# LoRa-Bee_v12.net
KiCad netlist of a schematic drawn in EAGLE
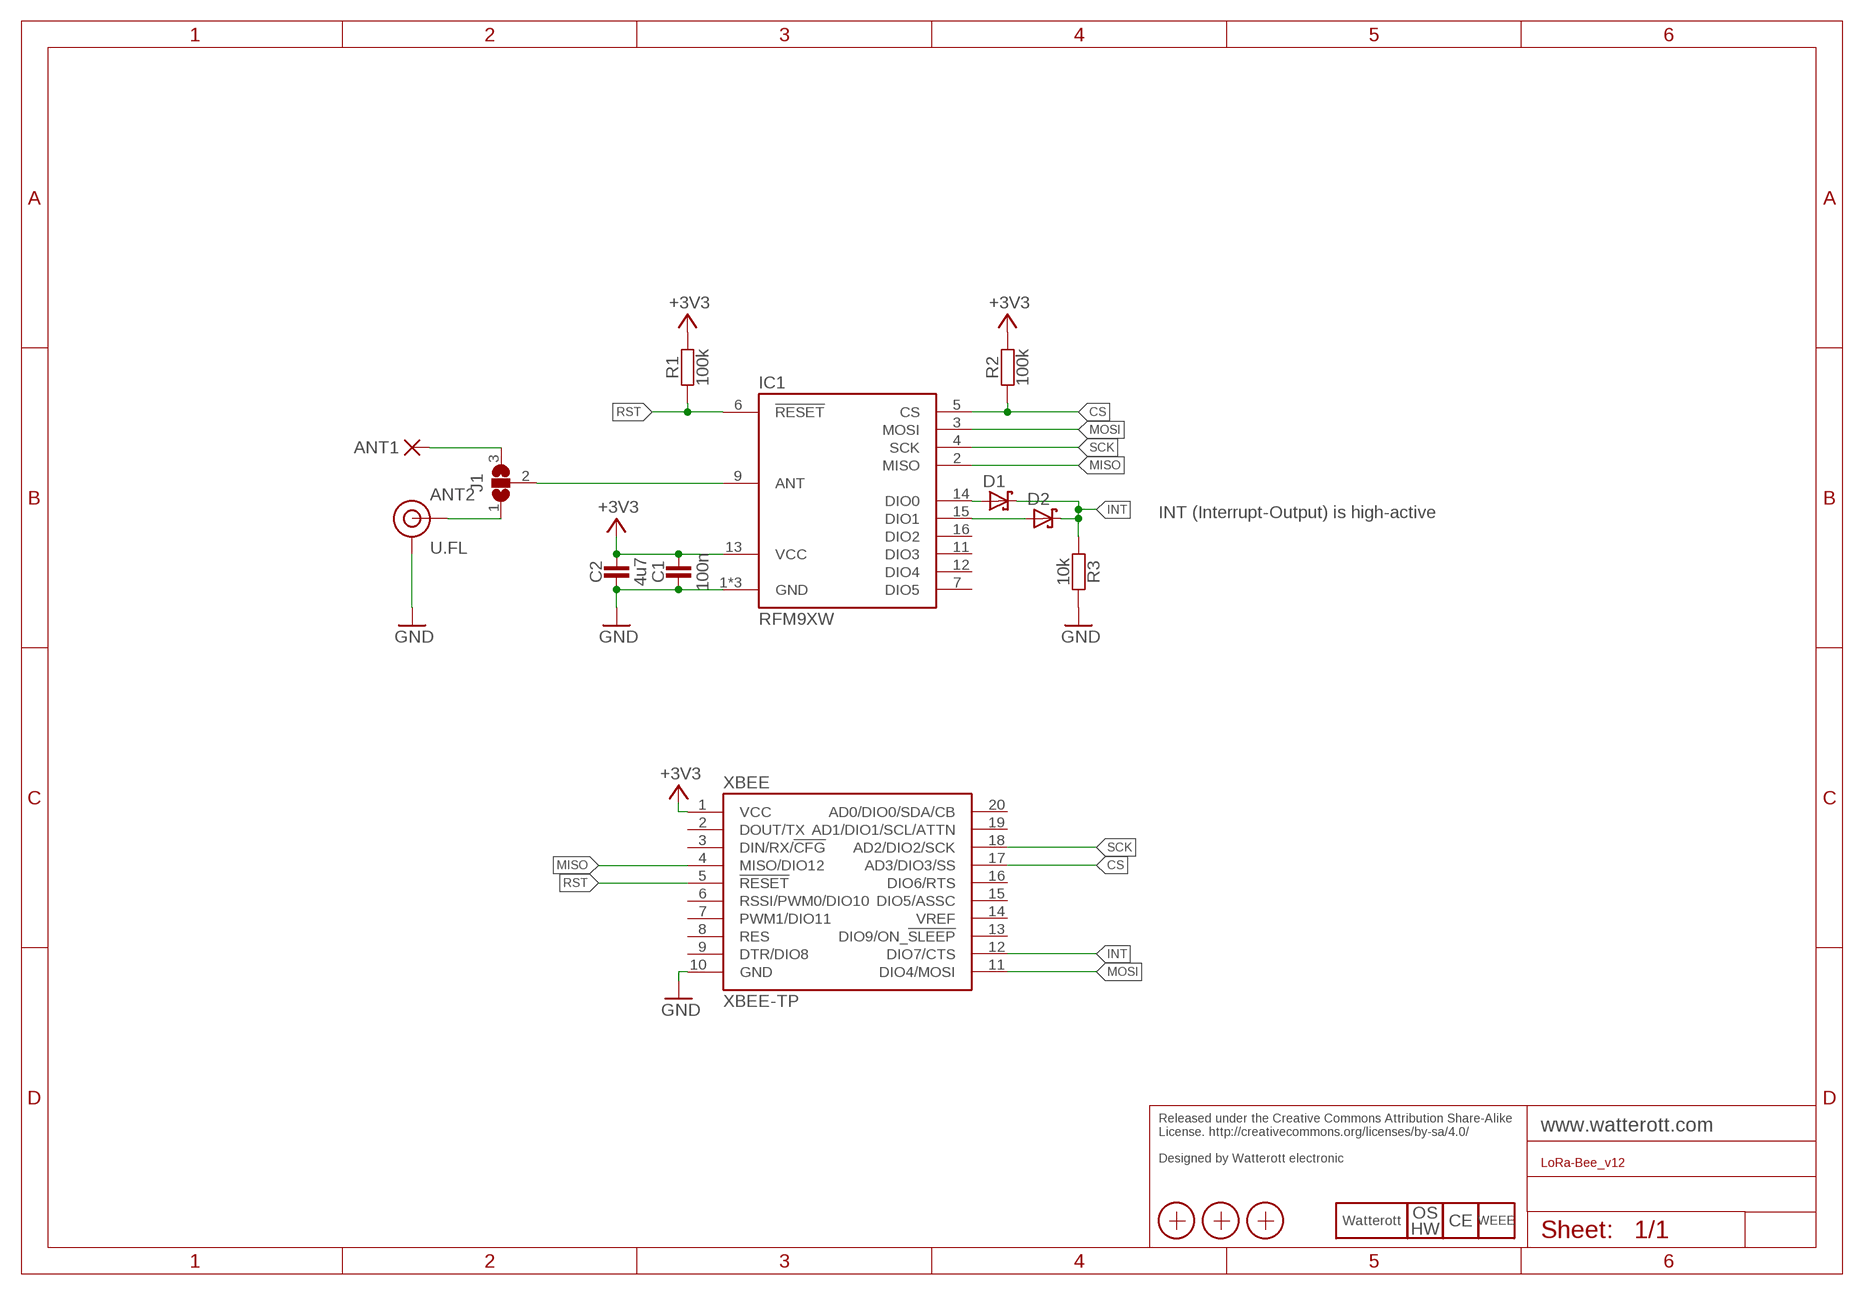
[diagram p0: schematic, sheet 1]

(export (version "E")
  (design (tool "Eeschema 10.0.6"))
  (components
    (comp (ref "ANT1")
      (value "PAD-1.00-1.60")
      (footprint "eagle-import:PAD-1.00-1.60")
      (libsource (lib "eagle-import") (part "PAD-1.00-1.60"))
    )
    (comp (ref "ANT2")
      (value "U.FL")
      (footprint "eagle-import:U.FL")
      (libsource (lib "eagle-import") (part "U.FL"))
    )
    (comp (ref "C1")
      (value "100n")
      (footprint "eagle-import:C0402")
      (libsource (lib "eagle-import") (part "CAPACITOR-0402"))
    )
    (comp (ref "C2")
      (value "4u7")
      (footprint "eagle-import:C0402")
      (libsource (lib "eagle-import") (part "CAPACITOR-0402"))
    )
    (comp (ref "D1")
      (value "D_SCHOTTKY-SOD532")
      (footprint "eagle-import:SOD523")
      (libsource (lib "eagle-import") (part "D_SCHOTTKY-SOD532"))
    )
    (comp (ref "D2")
      (value "D_SCHOTTKY-SOD532")
      (footprint "eagle-import:SOD523")
      (libsource (lib "eagle-import") (part "D_SCHOTTKY-SOD532"))
    )
    (comp (ref "IC1")
      (value "RFM9XW")
      (footprint "eagle-import:RFM9X")
      (libsource (lib "eagle-import") (part "RFM9XW"))
    )
    (comp (ref "J1")
      (value "JUMPER3-0603")
      (footprint "eagle-import:JUMPER3-0603")
      (libsource (lib "eagle-import") (part "JUMPER3-0603"))
    )
    (comp (ref "LOGO3")
      (value "LOGO_SPARK-2")
      (footprint "eagle-import:SPARK_2MM")
      (libsource (lib "eagle-import") (part "LOGO_SPARK-2"))
    )
    (comp (ref "LOGO4")
      (value "LOGO_OSHW-2")
      (footprint "eagle-import:OSHW_2MM")
      (libsource (lib "eagle-import") (part "LOGO_OSHW-2"))
    )
    (comp (ref "LOGO5")
      (value "LOGO_CE-2")
      (footprint "eagle-import:CE_2MM")
      (libsource (lib "eagle-import") (part "LOGO_CE-2"))
    )
    (comp (ref "LOGO6")
      (value "LOGO_WEEE-4")
      (footprint "eagle-import:WEEE_4MM")
      (libsource (lib "eagle-import") (part "LOGO_WEEE-4"))
    )
    (comp (ref "R1")
      (value "100k")
      (footprint "eagle-import:C0402")
      (libsource (lib "eagle-import") (part "RESISTOR-0402"))
    )
    (comp (ref "R2")
      (value "100k")
      (footprint "eagle-import:C0402")
      (libsource (lib "eagle-import") (part "RESISTOR-0402"))
    )
    (comp (ref "R3")
      (value "10k")
      (footprint "eagle-import:C0402")
      (libsource (lib "eagle-import") (part "RESISTOR-0402"))
    )
    (comp (ref "X1")
      (value "PASSER-07")
      (footprint "eagle-import:PASSER_07MM")
      (libsource (lib "eagle-import") (part "PASSER-07"))
    )
    (comp (ref "X2")
      (value "PASSER-07")
      (footprint "eagle-import:PASSER_07MM")
      (libsource (lib "eagle-import") (part "PASSER-07"))
    )
    (comp (ref "X3")
      (value "PASSER-07")
      (footprint "eagle-import:PASSER_07MM")
      (libsource (lib "eagle-import") (part "PASSER-07"))
    )
    (comp (ref "XBEE")
      (value "XBEE-TP")
      (footprint "eagle-import:XBEE_TP")
      (libsource (lib "eagle-import") (part "XBEE-TP"))
    )
  )
  (nets
    (net (code "1") (name "+3V3") (class "Default")
      (node (ref "C1") (pin "2") (pinfunction "2_2") (pintype "passive"))
      (node (ref "C2") (pin "2") (pinfunction "2_2") (pintype "passive"))
      (node (ref "IC1") (pin "13") (pinfunction "VCC_13") (pintype "power_in"))
      (node (ref "R1") (pin "2") (pinfunction "2_2") (pintype "passive"))
      (node (ref "R2") (pin "2") (pinfunction "2_2") (pintype "passive"))
      (node (ref "XBEE") (pin "1") (pinfunction "VCC_1") (pintype "power_in"))
    )
    (net (code "2") (name "CS") (class "Default")
      (node (ref "IC1") (pin "5") (pinfunction "CS_5") (pintype "input"))
      (node (ref "R2") (pin "1") (pinfunction "1_1") (pintype "passive"))
      (node (ref "XBEE") (pin "17") (pinfunction "AD3/DIO3/SS_17") (pintype "bidirectional"))
    )
    (net (code "3") (name "GND") (class "Default")
      (node (ref "ANT2") (pin "1") (pinfunction "GND_1") (pintype "bidirectional"))
      (node (ref "ANT2") (pin "2") (pinfunction "GND_2") (pintype "bidirectional"))
      (node (ref "C1") (pin "1") (pinfunction "1_1") (pintype "passive"))
      (node (ref "C2") (pin "1") (pinfunction "1_1") (pintype "passive"))
      (node (ref "IC1") (pin "1") (pinfunction "GND_1") (pintype "power_in"))
      (node (ref "IC1") (pin "10") (pinfunction "GND_10") (pintype "power_in"))
      (node (ref "IC1") (pin "8") (pinfunction "GND_8") (pintype "power_in"))
      (node (ref "R3") (pin "2") (pinfunction "2_2") (pintype "passive"))
      (node (ref "XBEE") (pin "10") (pinfunction "GND_10") (pintype "power_in"))
    )
    (net (code "4") (name "INT") (class "Default")
      (node (ref "D1") (pin "C") (pinfunction "C_C") (pintype "passive"))
      (node (ref "D2") (pin "C") (pinfunction "C_C") (pintype "passive"))
      (node (ref "R3") (pin "1") (pinfunction "1_1") (pintype "passive"))
      (node (ref "XBEE") (pin "12") (pinfunction "DIO7/CTS_12") (pintype "bidirectional"))
    )
    (net (code "5") (name "MISO") (class "Default")
      (node (ref "IC1") (pin "2") (pinfunction "MISO_2") (pintype "output"))
      (node (ref "XBEE") (pin "4") (pinfunction "MISO/DIO12_4") (pintype "bidirectional"))
    )
    (net (code "6") (name "MOSI") (class "Default")
      (node (ref "IC1") (pin "3") (pinfunction "MOSI_3") (pintype "input"))
      (node (ref "XBEE") (pin "11") (pinfunction "DIO4/MOSI_11") (pintype "bidirectional"))
    )
    (net (code "7") (name "Net-(ANT1-P)") (class "Default")
      (node (ref "ANT1") (pin "1") (pinfunction "P_1") (pintype "passive"))
      (node (ref "J1") (pin "3") (pinfunction "3_3") (pintype "passive"))
    )
    (net (code "8") (name "Net-(ANT2-SIGNAL)") (class "Default")
      (node (ref "ANT2") (pin "FEED") (pinfunction "SIGNAL_FEED") (pintype "bidirectional"))
      (node (ref "J1") (pin "1") (pinfunction "1_1") (pintype "passive"))
    )
    (net (code "9") (name "Net-(IC1-ANT)") (class "Default")
      (node (ref "IC1") (pin "9") (pinfunction "ANT_9") (pintype "bidirectional"))
      (node (ref "J1") (pin "2") (pinfunction "2_2") (pintype "passive"))
    )
    (net (code "10") (name "Net-(IC1-DIO0)") (class "Default")
      (node (ref "D1") (pin "A") (pinfunction "A_A") (pintype "passive"))
      (node (ref "IC1") (pin "14") (pinfunction "DIO0_14") (pintype "bidirectional"))
    )
    (net (code "11") (name "Net-(IC1-DIO1)") (class "Default")
      (node (ref "D2") (pin "A") (pinfunction "A_A") (pintype "passive"))
      (node (ref "IC1") (pin "15") (pinfunction "DIO1_15") (pintype "bidirectional"))
    )
    (net (code "12") (name "RST") (class "Default")
      (node (ref "IC1") (pin "6") (pinfunction "~{RESET}_6") (pintype "input"))
      (node (ref "R1") (pin "1") (pinfunction "1_1") (pintype "passive"))
      (node (ref "XBEE") (pin "5") (pinfunction "~{RESET}_5") (pintype "bidirectional"))
    )
    (net (code "13") (name "SCK") (class "Default")
      (node (ref "IC1") (pin "4") (pinfunction "SCK_4") (pintype "input"))
      (node (ref "XBEE") (pin "18") (pinfunction "AD2/DIO2/SCK_18") (pintype "bidirectional"))
    )
    (net (code "14") (name "unconnected-(IC1-DIO2-Pad16)") (class "Default")
      (node (ref "IC1") (pin "16") (pinfunction "DIO2_16") (pintype "bidirectional"))
    )
    (net (code "15") (name "unconnected-(IC1-DIO3-Pad11)") (class "Default")
      (node (ref "IC1") (pin "11") (pinfunction "DIO3_11") (pintype "bidirectional"))
    )
    (net (code "16") (name "unconnected-(IC1-DIO4-Pad12)") (class "Default")
      (node (ref "IC1") (pin "12") (pinfunction "DIO4_12") (pintype "bidirectional"))
    )
    (net (code "17") (name "unconnected-(IC1-DIO5-Pad7)") (class "Default")
      (node (ref "IC1") (pin "7") (pinfunction "DIO5_7") (pintype "bidirectional"))
    )
    (net (code "18") (name "unconnected-(XBEE-AD0{slash}DIO0{slash}SDA{slash}CB-Pad20)") (class "Default")
      (node (ref "XBEE") (pin "20") (pinfunction "AD0/DIO0/SDA/CB_20") (pintype "bidirectional"))
    )
    (net (code "19") (name "unconnected-(XBEE-AD1{slash}DIO1{slash}SCL{slash}ATTN-Pad19)") (class "Default")
      (node (ref "XBEE") (pin "19") (pinfunction "AD1/DIO1/SCL/ATTN_19") (pintype "bidirectional"))
    )
    (net (code "20") (name "unconnected-(XBEE-DIN{slash}RX{slash}~{CFG}-Pad3)") (class "Default")
      (node (ref "XBEE") (pin "3") (pinfunction "DIN/RX/~{CFG}_3") (pintype "bidirectional"))
    )
    (net (code "21") (name "unconnected-(XBEE-DIO5{slash}ASSC-Pad15)") (class "Default")
      (node (ref "XBEE") (pin "15") (pinfunction "DIO5/ASSC_15") (pintype "bidirectional"))
    )
    (net (code "22") (name "unconnected-(XBEE-DIO6{slash}RTS-Pad16)") (class "Default")
      (node (ref "XBEE") (pin "16") (pinfunction "DIO6/RTS_16") (pintype "bidirectional"))
    )
    (net (code "23") (name "unconnected-(XBEE-DIO9{slash}ON_~{SLEEP}-Pad13)") (class "Default")
      (node (ref "XBEE") (pin "13") (pinfunction "DIO9/ON_~{SLEEP}_13") (pintype "bidirectional"))
    )
    (net (code "24") (name "unconnected-(XBEE-DOUT{slash}TX-Pad2)") (class "Default")
      (node (ref "XBEE") (pin "2") (pinfunction "DOUT/TX_2") (pintype "bidirectional"))
    )
    (net (code "25") (name "unconnected-(XBEE-DTR{slash}DIO8-Pad9)") (class "Default")
      (node (ref "XBEE") (pin "9") (pinfunction "DTR/DIO8_9") (pintype "bidirectional"))
    )
    (net (code "26") (name "unconnected-(XBEE-PWM1{slash}DIO11-Pad7)") (class "Default")
      (node (ref "XBEE") (pin "7") (pinfunction "PWM1/DIO11_7") (pintype "bidirectional"))
    )
    (net (code "27") (name "unconnected-(XBEE-RES-Pad8)") (class "Default")
      (node (ref "XBEE") (pin "8") (pinfunction "RES_8") (pintype "bidirectional"))
    )
    (net (code "28") (name "unconnected-(XBEE-RSSI{slash}PWM0{slash}DIO10-Pad6)") (class "Default")
      (node (ref "XBEE") (pin "6") (pinfunction "RSSI/PWM0/DIO10_6") (pintype "bidirectional"))
    )
    (net (code "29") (name "unconnected-(XBEE-VREF-Pad14)") (class "Default")
      (node (ref "XBEE") (pin "14") (pinfunction "VREF_14") (pintype "bidirectional"))
    )
  )
)
